# conn_usbc.net
KiCad netlist of a schematic drawn in Altium Designer
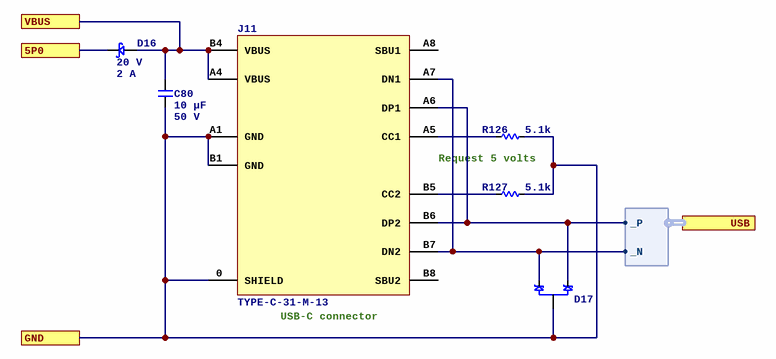
[diagram p0: conn_usbc.SchDoc]

(export (version "E")
  (design (tool "Eeschema 10.0.6"))
  (components
    (comp (ref "C80")
      (value "CL31B106KBHNNNE")
      (footprint "C1206")
      (fields
        (field (name "CAPACITANCE") "10 µF")
        (field (name "MANUFACTURER") "Samsung Electro-Mechanics")
        (field (name "VOLTAGE RATING") "50 V")
      )
      (libsource (lib "database") (part "__template_cap"))
    )
    (comp (ref "D16")
      (value "MSS2P2-M3/89A")
      (footprint "ESMP")
      (description "DIODE SCHOTTKY 20V 2A MICROSMP")
      (fields
        (field (name "MANUFACTURER") "Vishay Semiconductor Diodes Division")
        (field (name "VR") "20 V")
        (field (name "CURRENT") "2 A")
      )
      (libsource (lib "database") (part "__template_diode_schottky"))
    )
    (comp (ref "D17")
      (value "PESD2USB3UX")
      (footprint "3SOT23")
      (description "DIODE ESD USB SOT-23")
      (fields (field (name "MANUFACTURER") "Nexperia USA Inc."))
      (libsource (lib "database") (part "PESD2USB3UX"))
    )
    (comp (ref "J11")
      (value "TYPE-C-31-M-13")
      (footprint "CONN_USBC_TYPE-C-31-M-13")
      (description "USB 2.0 12P USB-C connector")
      (fields (field (name "MANUFACTURER") "HRO Electronics"))
      (libsource (lib "database") (part "TYPE-C-31-M-13"))
    )
    (comp (ref "R126")
      (value "5.1k")
      (footprint "R0402")
      (fields
        (field (name "TOLERANCE") "1%")
        (field (name "MANUFACTURER PART NUMBER") "0402WGF5101TCE")
        (field (name "MANUFACTURER") "UNI-ROYAL(Uniroyal Elec)")
      )
      (libsource (lib "database") (part "__template_resistor"))
    )
    (comp (ref "R127")
      (value "5.1k")
      (footprint "R0402")
      (fields
        (field (name "TOLERANCE") "1%")
        (field (name "MANUFACTURER PART NUMBER") "0402WGF5101TCE")
        (field (name "MANUFACTURER") "UNI-ROYAL(Uniroyal Elec)")
      )
      (libsource (lib "database") (part "__template_resistor"))
    )
  )
  (nets
    (net (code "2") (name "/5P0") (class "Default") (node (ref "D16") (pin "2") (pintype "passive")))
    (net (code "3") (name "/GND") (class "Default")
      (node (ref "C80") (pin "2") (pintype "passive"))
      (node (ref "D17") (pin "3") (pintype "passive"))
      (node (ref "J11") (pin "0") (pinfunction "SHIELD_0") (pintype "power_in"))
      (node (ref "J11") (pin "A1") (pinfunction "GND_A1") (pintype "power_in"))
      (node (ref "J11") (pin "B1") (pinfunction "GND_B1") (pintype "power_in"))
      (node (ref "R126") (pin "1") (pintype "passive"))
      (node (ref "R127") (pin "1") (pintype "passive"))
    )
    (net (code "4") (name "/VBUS") (class "Default")
      (node (ref "C80") (pin "1") (pintype "passive"))
      (node (ref "D16") (pin "1") (pintype "passive"))
      (node (ref "J11") (pin "A4") (pinfunction "VBUS_A4") (pintype "power_in"))
      (node (ref "J11") (pin "B4") (pinfunction "VBUS_B4") (pintype "passive"))
    )
    (net (code "6") (name "Net-(J11-CC1)") (class "Default")
      (node (ref "J11") (pin "A5") (pinfunction "CC1_A5") (pintype "passive"))
      (node (ref "R126") (pin "2") (pintype "passive"))
    )
    (net (code "7") (name "Net-(J11-CC2)") (class "Default")
      (node (ref "J11") (pin "B5") (pinfunction "CC2_B5") (pintype "passive"))
      (node (ref "R127") (pin "2") (pintype "passive"))
    )
    (net (code "8") (name "Net-(J11-DN1)") (class "Default")
      (node (ref "D17") (pin "1") (pintype "passive"))
      (node (ref "J11") (pin "A7") (pinfunction "DN1_A7") (pintype "passive"))
      (node (ref "J11") (pin "B7") (pinfunction "DN2_B7") (pintype "passive"))
    )
    (net (code "9") (name "Net-(J11-DP1)") (class "Default")
      (node (ref "D17") (pin "2") (pintype "passive"))
      (node (ref "J11") (pin "A6") (pinfunction "DP1_A6") (pintype "passive"))
      (node (ref "J11") (pin "B6") (pinfunction "DP2_B6") (pintype "passive"))
    )
    (net (code "10") (name "unconnected-(J11-SBU1-PadA8)") (class "Default")
      (node (ref "J11") (pin "A8") (pinfunction "SBU1_A8") (pintype "passive"))
    )
    (net (code "11") (name "unconnected-(J11-SBU2-PadB8)") (class "Default")
      (node (ref "J11") (pin "B8") (pinfunction "SBU2_B8") (pintype "passive"))
    )
  )
)
